# 5_hardware.net
KiCad netlist of a schematic drawn in Altium Designer
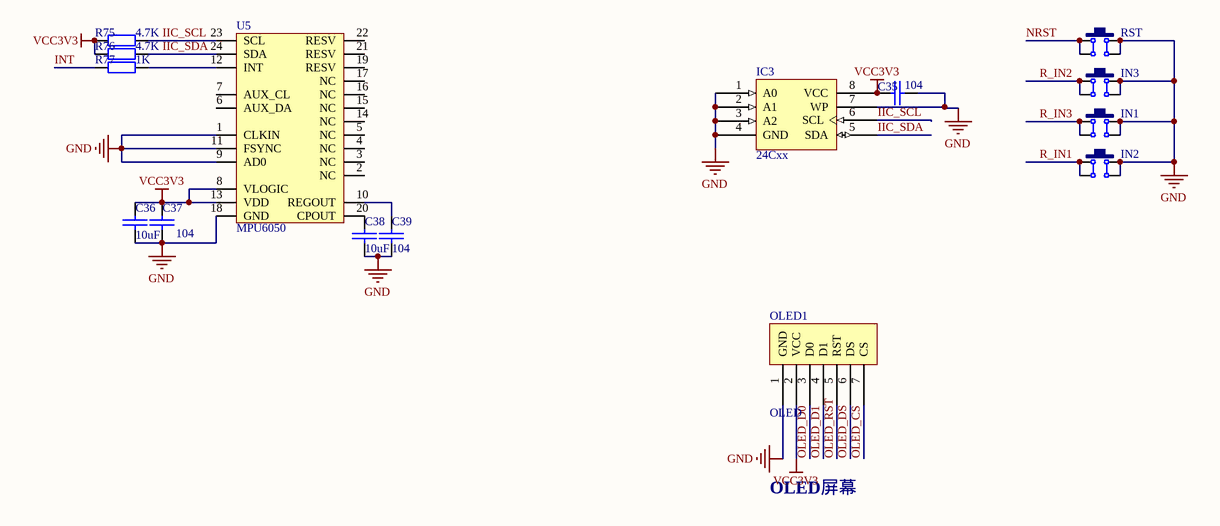
[diagram p0: 5_hardware.SchDoc]

(export (version "E")
  (design (tool "Eeschema 10.0.6"))
  (components
    (comp (ref "C35")
      (value "104")
      (footprint "LC-0603_C")
      (description "Capacitor 0805")
      (libsource (lib "CD's_LIB_2018") (part "0805C"))
    )
    (comp (ref "C36")
      (value "10uF")
      (footprint "LC-0805_C")
      (description "Capacitor 0805")
      (libsource (lib "CD's_LIB_2018") (part "0805C"))
    )
    (comp (ref "C37")
      (value "104")
      (footprint "LC-0603_C")
      (description "Capacitor 0805")
      (libsource (lib "CD's_LIB_2018") (part "0805C"))
    )
    (comp (ref "C38")
      (value "10uF")
      (footprint "LC-0805_C")
      (description "Capacitor 0805")
      (libsource (lib "CD's_LIB_2018") (part "0805C"))
    )
    (comp (ref "C39")
      (value "104")
      (footprint "LC-0603_C")
      (description "Capacitor 0805")
      (libsource (lib "CD's_LIB_2018") (part "0805C"))
    )
    (comp (ref "IC3")
      (value "24Cxx")
      (footprint "SOP8_M")
      (description "外置EEPROM")
      (fields (field (name "版权归属") "源创客"))
      (libsource (lib "1.1   - IC芯片") (part "24Cxx"))
    )
    (comp (ref "IN1")
      (value "6x6x5")
      (footprint "TSW DIP-6*6*6")
      (description "直插6x6轻触开关")
      (fields (field (name "版权归属") "源创客"))
      (libsource (lib "5.1   - 按键-开关") (part "TSW DIP-6x6"))
    )
    (comp (ref "IN2")
      (value "6x6x5")
      (footprint "TSW DIP-6*6*6")
      (description "直插6x6轻触开关")
      (fields (field (name "版权归属") "源创客"))
      (libsource (lib "5.1   - 按键-开关") (part "TSW DIP-6x6"))
    )
    (comp (ref "IN3")
      (value "6x6x5")
      (footprint "TSW DIP-6*6*6")
      (description "直插6x6轻触开关")
      (fields (field (name "版权归属") "源创客"))
      (libsource (lib "5.1   - 按键-开关") (part "TSW DIP-6x6"))
    )
    (comp (ref "OLED1")
      (value "OLED")
      (footprint "OLED-0.96")
      (description "OLED屏幕")
      (libsource (lib "9.2   - 显示器件") (part "OLED_SPI"))
    )
    (comp (ref "R75")
      (value "4.7K")
      (footprint "LC-0603_R")
      (description "贴片电阻")
      (fields (field (name "PUBLISHER") "Altium Limited"))
      (libsource (lib "liu_2016") (part "Res1"))
    )
    (comp (ref "R76")
      (value "4.7K")
      (footprint "LC-0603_R")
      (description "贴片电阻")
      (fields (field (name "PUBLISHER") "Altium Limited"))
      (libsource (lib "liu_2016") (part "Res1"))
    )
    (comp (ref "R77")
      (value "1K")
      (footprint "LC-0603_R")
      (description "贴片电阻")
      (fields (field (name "PUBLISHER") "Altium Limited"))
      (libsource (lib "liu_2016") (part "Res1"))
    )
    (comp (ref "RST")
      (value "6x6x5")
      (footprint "TSW DIP-6*6*6")
      (description "直插6x6轻触开关")
      (fields (field (name "版权归属") "源创客"))
      (libsource (lib "5.1   - 按键-开关") (part "TSW DIP-6x6"))
    )
    (comp (ref "U5")
      (value "MPU6050")
      (footprint "QFN24 4x4_M")
      (description "9轴运动处理传感器")
      (libsource (lib "Explorer STM32F407封装库") (part "MPU6050"))
    )
  )
  (nets
    (net (code "1") (name "/IIC_SCL") (class "Default")
      (node (ref "IC3") (pin "6") (pinfunction "SCL_6") (pintype "input"))
      (node (ref "R75") (pin "1") (pinfunction "1_1") (pintype "passive"))
      (node (ref "U5") (pin "23") (pinfunction "SCL_23") (pintype "passive"))
    )
    (net (code "2") (name "/IIC_SDA") (class "Default")
      (node (ref "IC3") (pin "5") (pinfunction "SDA_5") (pintype "bidirectional"))
      (node (ref "R76") (pin "1") (pinfunction "1_1") (pintype "passive"))
      (node (ref "U5") (pin "24") (pinfunction "SDA_24") (pintype "passive"))
    )
    (net (code "3") (name "/INT") (class "Default")
      (node (ref "R77") (pin "2") (pinfunction "2_2") (pintype "passive"))
    )
    (net (code "4") (name "/NRST") (class "Default")
      (node (ref "RST") (pin "1") (pinfunction "1_1") (pintype "passive"))
      (node (ref "RST") (pin "4") (pinfunction "4_4") (pintype "passive"))
    )
    (net (code "5") (name "/OLED_CS") (class "Default")
      (node (ref "OLED1") (pin "7") (pinfunction "CS_7") (pintype "passive"))
    )
    (net (code "6") (name "/OLED_D0") (class "Default")
      (node (ref "OLED1") (pin "3") (pinfunction "D0_3") (pintype "passive"))
    )
    (net (code "7") (name "/OLED_D1") (class "Default")
      (node (ref "OLED1") (pin "4") (pinfunction "D1_4") (pintype "passive"))
    )
    (net (code "8") (name "/OLED_DS") (class "Default")
      (node (ref "OLED1") (pin "6") (pinfunction "DS_6") (pintype "passive"))
    )
    (net (code "9") (name "/OLED_RST") (class "Default")
      (node (ref "OLED1") (pin "5") (pinfunction "RST_5") (pintype "passive"))
    )
    (net (code "10") (name "/R_IN1") (class "Default")
      (node (ref "IN2") (pin "1") (pinfunction "1_1") (pintype "passive"))
      (node (ref "IN2") (pin "4") (pinfunction "4_4") (pintype "passive"))
    )
    (net (code "11") (name "/R_IN2") (class "Default")
      (node (ref "IN3") (pin "1") (pinfunction "1_1") (pintype "passive"))
      (node (ref "IN3") (pin "4") (pinfunction "4_4") (pintype "passive"))
    )
    (net (code "12") (name "/R_IN3") (class "Default")
      (node (ref "IN1") (pin "1") (pinfunction "1_1") (pintype "passive"))
      (node (ref "IN1") (pin "4") (pinfunction "4_4") (pintype "passive"))
    )
    (net (code "13") (name "GND") (class "Default")
      (node (ref "C35") (pin "1") (pinfunction "1_1") (pintype "passive"))
      (node (ref "C36") (pin "1") (pinfunction "1_1") (pintype "passive"))
      (node (ref "C37") (pin "1") (pinfunction "1_1") (pintype "passive"))
      (node (ref "C38") (pin "1") (pinfunction "1_1") (pintype "passive"))
      (node (ref "C39") (pin "2") (pinfunction "2_2") (pintype "passive"))
      (node (ref "IC3") (pin "1") (pinfunction "A0_1") (pintype "input"))
      (node (ref "IC3") (pin "2") (pinfunction "A1_2") (pintype "input"))
      (node (ref "IC3") (pin "3") (pinfunction "A2_3") (pintype "input"))
      (node (ref "IC3") (pin "4") (pinfunction "GND_4") (pintype "passive"))
      (node (ref "IC3") (pin "7") (pinfunction "WP_7") (pintype "passive"))
      (node (ref "IN1") (pin "2") (pinfunction "2_2") (pintype "passive"))
      (node (ref "IN1") (pin "3") (pinfunction "3_3") (pintype "passive"))
      (node (ref "IN2") (pin "2") (pinfunction "2_2") (pintype "passive"))
      (node (ref "IN2") (pin "3") (pinfunction "3_3") (pintype "passive"))
      (node (ref "IN3") (pin "2") (pinfunction "2_2") (pintype "passive"))
      (node (ref "IN3") (pin "3") (pinfunction "3_3") (pintype "passive"))
      (node (ref "OLED1") (pin "1") (pinfunction "GND_1") (pintype "passive"))
      (node (ref "RST") (pin "2") (pinfunction "2_2") (pintype "passive"))
      (node (ref "RST") (pin "3") (pinfunction "3_3") (pintype "passive"))
      (node (ref "U5") (pin "1") (pinfunction "CLKIN_1") (pintype "passive"))
      (node (ref "U5") (pin "11") (pinfunction "FSYNC_11") (pintype "passive"))
      (node (ref "U5") (pin "18") (pinfunction "GND_18") (pintype "passive"))
      (node (ref "U5") (pin "9") (pinfunction "AD0_9") (pintype "passive"))
    )
    (net (code "14") (name "Net-(U5-CPOUT)") (class "Default")
      (node (ref "C38") (pin "2") (pinfunction "2_2") (pintype "passive"))
      (node (ref "U5") (pin "20") (pinfunction "CPOUT_20") (pintype "passive"))
    )
    (net (code "15") (name "Net-(U5-INT)") (class "Default")
      (node (ref "R77") (pin "1") (pinfunction "1_1") (pintype "passive"))
      (node (ref "U5") (pin "12") (pinfunction "INT_12") (pintype "passive"))
    )
    (net (code "16") (name "Net-(U5-REGOUT)") (class "Default")
      (node (ref "C39") (pin "1") (pinfunction "1_1") (pintype "passive"))
      (node (ref "U5") (pin "10") (pinfunction "REGOUT_10") (pintype "passive"))
    )
    (net (code "17") (name "VCC3V3") (class "Default")
      (node (ref "C35") (pin "2") (pinfunction "2_2") (pintype "passive"))
      (node (ref "C36") (pin "2") (pinfunction "2_2") (pintype "passive"))
      (node (ref "C37") (pin "2") (pinfunction "2_2") (pintype "passive"))
      (node (ref "IC3") (pin "8") (pinfunction "VCC_8") (pintype "power_in"))
      (node (ref "OLED1") (pin "2") (pinfunction "VCC_2") (pintype "passive"))
      (node (ref "R75") (pin "2") (pinfunction "2_2") (pintype "passive"))
      (node (ref "R76") (pin "2") (pinfunction "2_2") (pintype "passive"))
      (node (ref "U5") (pin "13") (pinfunction "VDD_13") (pintype "passive"))
      (node (ref "U5") (pin "8") (pinfunction "VLOGIC_8") (pintype "passive"))
    )
    (net (code "18") (name "unconnected-(U5-AUX_CL-Pad7)") (class "Default")
      (node (ref "U5") (pin "7") (pinfunction "AUX_CL_7") (pintype "passive"))
    )
    (net (code "19") (name "unconnected-(U5-AUX_DA-Pad6)") (class "Default")
      (node (ref "U5") (pin "6") (pinfunction "AUX_DA_6") (pintype "passive"))
    )
    (net (code "20") (name "unconnected-(U5-NC-Pad2)") (class "Default")
      (node (ref "U5") (pin "2") (pinfunction "NC_2") (pintype "passive"))
    )
    (net (code "21") (name "unconnected-(U5-NC-Pad3)") (class "Default")
      (node (ref "U5") (pin "3") (pinfunction "NC_3") (pintype "passive"))
    )
    (net (code "22") (name "unconnected-(U5-NC-Pad4)") (class "Default")
      (node (ref "U5") (pin "4") (pinfunction "NC_4") (pintype "passive"))
    )
    (net (code "23") (name "unconnected-(U5-NC-Pad5)") (class "Default")
      (node (ref "U5") (pin "5") (pinfunction "NC_5") (pintype "passive"))
    )
    (net (code "24") (name "unconnected-(U5-NC-Pad14)") (class "Default")
      (node (ref "U5") (pin "14") (pinfunction "NC_14") (pintype "passive"))
    )
    (net (code "25") (name "unconnected-(U5-NC-Pad15)") (class "Default")
      (node (ref "U5") (pin "15") (pinfunction "NC_15") (pintype "passive"))
    )
    (net (code "26") (name "unconnected-(U5-NC-Pad16)") (class "Default")
      (node (ref "U5") (pin "16") (pinfunction "NC_16") (pintype "passive"))
    )
    (net (code "27") (name "unconnected-(U5-NC-Pad17)") (class "Default")
      (node (ref "U5") (pin "17") (pinfunction "NC_17") (pintype "passive"))
    )
    (net (code "28") (name "unconnected-(U5-RESV-Pad19)") (class "Default")
      (node (ref "U5") (pin "19") (pinfunction "RESV_19") (pintype "passive"))
    )
    (net (code "29") (name "unconnected-(U5-RESV-Pad21)") (class "Default")
      (node (ref "U5") (pin "21") (pinfunction "RESV_21") (pintype "passive"))
    )
    (net (code "30") (name "unconnected-(U5-RESV-Pad22)") (class "Default")
      (node (ref "U5") (pin "22") (pinfunction "RESV_22") (pintype "passive"))
    )
  )
)
